# Sheet1.net
KiCad netlist of a schematic drawn in Altium Designer
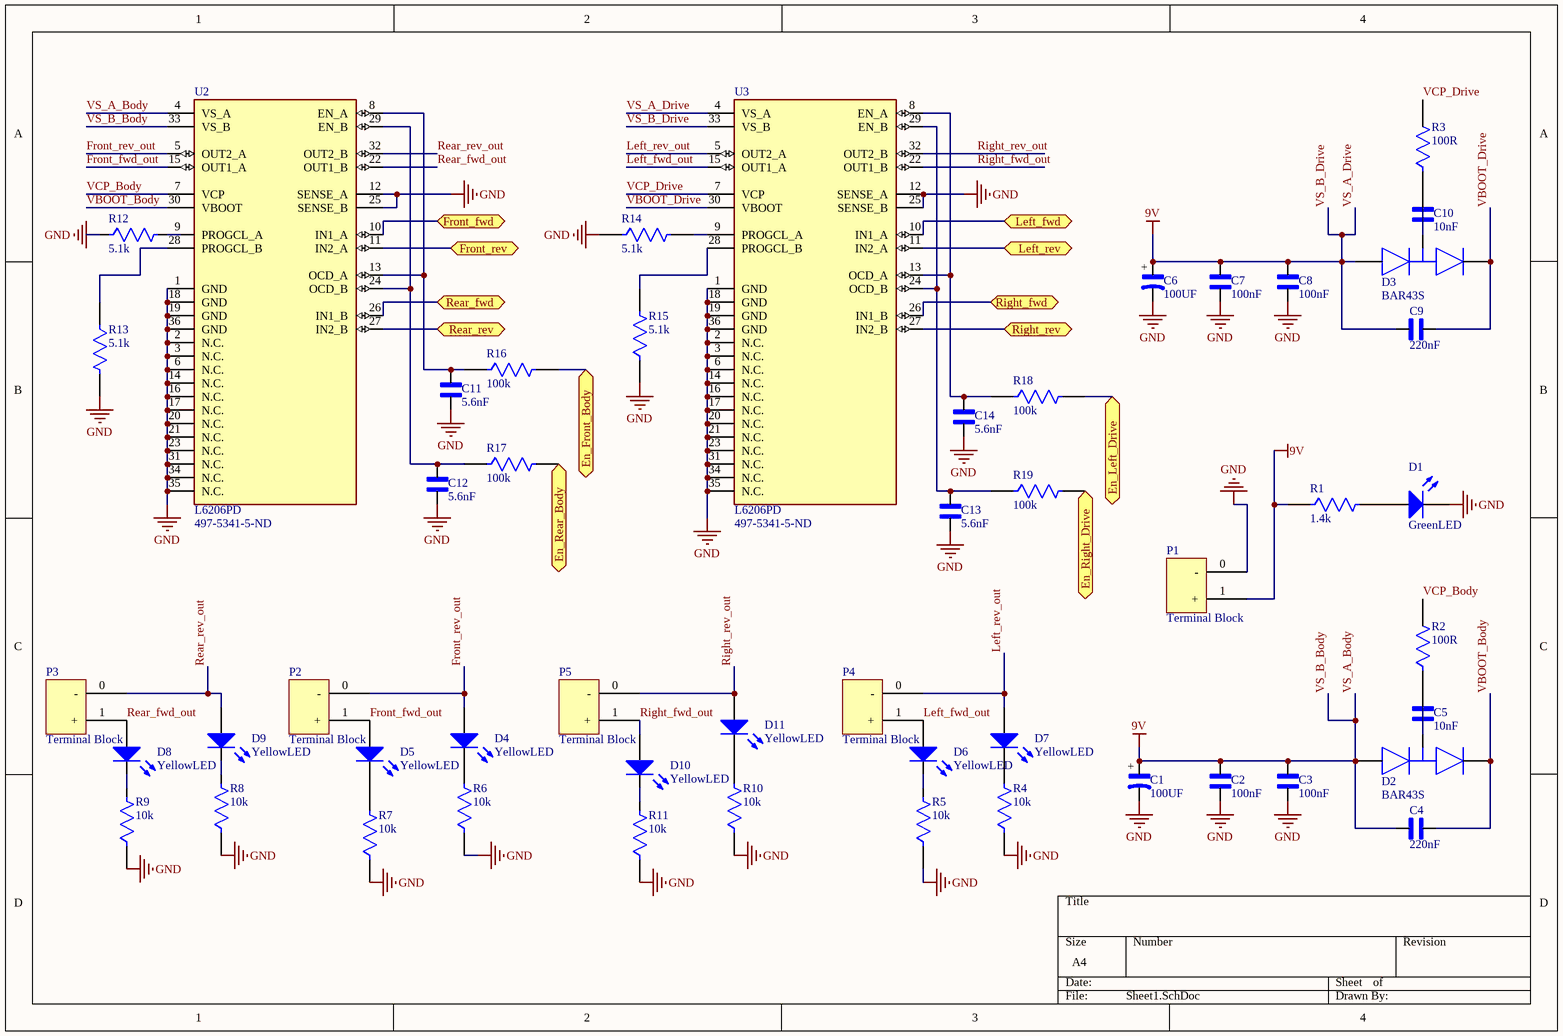
[diagram p0: Sheet1.SchDoc]

(export (version "E")
  (design (tool "Eeschema 10.0.6"))
  (components
    (comp (ref "C1")
      (value "100UF")
      (footprint "100UF")
      (description "Nichicon Aluminium Electrolytic Capacitor 100F 63 V 10mm Through Hole series VZ lifetime 1000h")
      (fields
        (field (name "MANUFACTURER") "Nichicon")
        (field (name "MANUFACTURER PART NUMBER") "UVZ1J101MPD1TD")
      )
      (libsource (lib "Schlib1") (part "100UF Capacitor"))
    )
    (comp (ref "C2")
      (value "100nF")
      (footprint "0402 Capacitor")
      (description "CAP CER 0.1UF 16V X7R 0402")
      (fields
        (field (name "MANUFACTURER") "Murata")
        (field (name "MANUFACTURER PART NUMBER") "GRM155R71C104KA88J")
      )
      (libsource (lib "Schlib1") (part "100nF Capacitor"))
    )
    (comp (ref "C3")
      (value "100nF")
      (footprint "0402 Capacitor")
      (description "CAP CER 0.1UF 16V X7R 0402")
      (fields
        (field (name "MANUFACTURER") "Murata")
        (field (name "MANUFACTURER PART NUMBER") "GRM155R71C104KA88J")
      )
      (libsource (lib "Schlib1") (part "100nF Capacitor"))
    )
    (comp (ref "C4")
      (value "220nF")
      (footprint "0805 Capacitor")
      (description "CAP CER 0805 220NF 100V X7R")
      (fields
        (field (name "MANUFACTURER") "KEMET")
        (field (name "MANUFACTURER PART NUMBER") "C0805C224K1RECAUTO")
      )
      (libsource (lib "Schlib1") (part "220nF Capacitor"))
    )
    (comp (ref "C5")
      (value "10nF")
      (footprint "0402 Capacitor")
      (description "CAP CER 10000PF 50V X7R 0402")
      (fields
        (field (name "MANUFACTURER") "KEMET")
        (field (name "MANUFACTURER PART NUMBER") "C0402C103M5RACTU")
      )
      (libsource (lib "Schlib1") (part "10nF Capacitor"))
    )
    (comp (ref "C6")
      (value "100UF")
      (footprint "100UF")
      (description "Nichicon Aluminium Electrolytic Capacitor 100F 63 V 10mm Through Hole series VZ lifetime 1000h")
      (fields
        (field (name "MANUFACTURER") "Nichicon")
        (field (name "MANUFACTURER PART NUMBER") "UVZ1J101MPD1TD")
      )
      (libsource (lib "Schlib1") (part "100UF Capacitor"))
    )
    (comp (ref "C7")
      (value "100nF")
      (footprint "0402 Capacitor")
      (description "CAP CER 0.1UF 16V X7R 0402")
      (fields
        (field (name "MANUFACTURER") "Murata")
        (field (name "MANUFACTURER PART NUMBER") "GRM155R71C104KA88J")
      )
      (libsource (lib "Schlib1") (part "100nF Capacitor"))
    )
    (comp (ref "C8")
      (value "100nF")
      (footprint "0402 Capacitor")
      (description "CAP CER 0.1UF 16V X7R 0402")
      (fields
        (field (name "MANUFACTURER") "Murata")
        (field (name "MANUFACTURER PART NUMBER") "GRM155R71C104KA88J")
      )
      (libsource (lib "Schlib1") (part "100nF Capacitor"))
    )
    (comp (ref "C9")
      (value "220nF")
      (footprint "0805 Capacitor")
      (description "CAP CER 0805 220NF 100V X7R")
      (fields
        (field (name "MANUFACTURER") "KEMET")
        (field (name "MANUFACTURER PART NUMBER") "C0805C224K1RECAUTO")
      )
      (libsource (lib "Schlib1") (part "220nF Capacitor"))
    )
    (comp (ref "C10")
      (value "10nF")
      (footprint "0402 Capacitor")
      (description "CAP CER 10000PF 50V X7R 0402")
      (fields
        (field (name "MANUFACTURER") "KEMET")
        (field (name "MANUFACTURER PART NUMBER") "C0402C103M5RACTU")
      )
      (libsource (lib "Schlib1") (part "10nF Capacitor"))
    )
    (comp (ref "C11")
      (value "5.6nF")
      (footprint "0402 Capacitor")
      (description "CAP CER 5600PF 25V X7R 0402")
      (fields
        (field (name "MANUFACTURER") "Yageo")
        (field (name "MANUFACTURER PART NUMBER") "CC0402KRX7R8BB562")
      )
      (libsource (lib "Schlib1") (part "5.6nF Capacitor"))
    )
    (comp (ref "C12")
      (value "5.6nF")
      (footprint "0402 Capacitor")
      (description "CAP CER 5600PF 25V X7R 0402")
      (fields
        (field (name "MANUFACTURER") "Yageo")
        (field (name "MANUFACTURER PART NUMBER") "CC0402KRX7R8BB562")
      )
      (libsource (lib "Schlib1") (part "5.6nF Capacitor"))
    )
    (comp (ref "C13")
      (value "5.6nF")
      (footprint "0402 Capacitor")
      (description "CAP CER 5600PF 25V X7R 0402")
      (fields
        (field (name "MANUFACTURER") "Yageo")
        (field (name "MANUFACTURER PART NUMBER") "CC0402KRX7R8BB562")
      )
      (libsource (lib "Schlib1") (part "5.6nF Capacitor"))
    )
    (comp (ref "C14")
      (value "5.6nF")
      (footprint "0402 Capacitor")
      (description "CAP CER 5600PF 25V X7R 0402")
      (fields
        (field (name "MANUFACTURER") "Yageo")
        (field (name "MANUFACTURER PART NUMBER") "CC0402KRX7R8BB562")
      )
      (libsource (lib "Schlib1") (part "5.6nF Capacitor"))
    )
    (comp (ref "D1")
      (value "GreenLED")
      (footprint "LED")
      (description "LED GREEN CLEAR SMD")
      (fields
        (field (name "MANUFACTURER") "Lumex")
        (field (name "MANUFACTURER PART NUMBER") "SML-LXFP0603SUGCTR")
      )
      (libsource (lib "Schlib1") (part "GreenLED"))
    )
    (comp (ref "D2")
      (value "BAR43S")
      (footprint "Double Diode")
      (fields
        (field (name "MANUFACTURER") "STMicroelectronics")
        (field (name "MANUFACTURER PART NUMBER") "BAR43SFILM")
      )
      (libsource (lib "Schlib1") (part "Diode Series"))
    )
    (comp (ref "D3")
      (value "BAR43S")
      (footprint "Double Diode")
      (fields
        (field (name "MANUFACTURER") "STMicroelectronics")
        (field (name "MANUFACTURER PART NUMBER") "BAR43SFILM")
      )
      (libsource (lib "Schlib1") (part "Diode Series"))
    )
    (comp (ref "D4")
      (value "YellowLED")
      (footprint "LED")
      (description "Led Yellow Clear 0603 SMD")
      (fields (field (name "MANUFACTURER") "Inolux") (field (name "MANUFACTURER PART NUMBER") "IN-S63AT5Y"))
      (libsource (lib "Schlib1") (part "YellowLED"))
    )
    (comp (ref "D5")
      (value "YellowLED")
      (footprint "LED")
      (description "Led Yellow Clear 0603 SMD")
      (fields (field (name "MANUFACTURER") "Inolux") (field (name "MANUFACTURER PART NUMBER") "IN-S63AT5Y"))
      (libsource (lib "Schlib1") (part "YellowLED"))
    )
    (comp (ref "D6")
      (value "YellowLED")
      (footprint "LED")
      (description "Led Yellow Clear 0603 SMD")
      (fields (field (name "MANUFACTURER") "Inolux") (field (name "MANUFACTURER PART NUMBER") "IN-S63AT5Y"))
      (libsource (lib "Schlib1") (part "YellowLED"))
    )
    (comp (ref "D7")
      (value "YellowLED")
      (footprint "LED")
      (description "Led Yellow Clear 0603 SMD")
      (fields (field (name "MANUFACTURER") "Inolux") (field (name "MANUFACTURER PART NUMBER") "IN-S63AT5Y"))
      (libsource (lib "Schlib1") (part "YellowLED"))
    )
    (comp (ref "D8")
      (value "YellowLED")
      (footprint "LED")
      (description "Led Yellow Clear 0603 SMD")
      (fields (field (name "MANUFACTURER") "Inolux") (field (name "MANUFACTURER PART NUMBER") "IN-S63AT5Y"))
      (libsource (lib "Schlib1") (part "YellowLED"))
    )
    (comp (ref "D9")
      (value "YellowLED")
      (footprint "LED")
      (description "Led Yellow Clear 0603 SMD")
      (fields (field (name "MANUFACTURER") "Inolux") (field (name "MANUFACTURER PART NUMBER") "IN-S63AT5Y"))
      (libsource (lib "Schlib1") (part "YellowLED"))
    )
    (comp (ref "D10")
      (value "YellowLED")
      (footprint "LED")
      (description "Led Yellow Clear 0603 SMD")
      (fields (field (name "MANUFACTURER") "Inolux") (field (name "MANUFACTURER PART NUMBER") "IN-S63AT5Y"))
      (libsource (lib "Schlib1") (part "YellowLED"))
    )
    (comp (ref "D11")
      (value "YellowLED")
      (footprint "LED")
      (description "Led Yellow Clear 0603 SMD")
      (fields (field (name "MANUFACTURER") "Inolux") (field (name "MANUFACTURER PART NUMBER") "IN-S63AT5Y"))
      (libsource (lib "Schlib1") (part "YellowLED"))
    )
    (comp (ref "P1")
      (value "Terminal Block")
      (footprint "PHOENIX_1935161")
      (description "Conn Terminal Blocks 2 POS 5mm Solder ST Thru-Hole 16A")
      (fields
        (field (name "MANUFACTURER") "Phoenix Contact")
        (field (name "MANUFACTURER PART NUMBER") "1935161")
      )
      (libsource (lib "Schlib1") (part "1935161"))
    )
    (comp (ref "P2")
      (value "Terminal Block")
      (footprint "PHOENIX_1935161")
      (description "Conn Terminal Blocks 2 POS 5mm Solder ST Thru-Hole 16A")
      (fields
        (field (name "MANUFACTURER") "Phoenix Contact")
        (field (name "MANUFACTURER PART NUMBER") "1935161")
      )
      (libsource (lib "Schlib1") (part "1935161"))
    )
    (comp (ref "P3")
      (value "Terminal Block")
      (footprint "PHOENIX_1935161")
      (description "Conn Terminal Blocks 2 POS 5mm Solder ST Thru-Hole 16A")
      (fields
        (field (name "MANUFACTURER") "Phoenix Contact")
        (field (name "MANUFACTURER PART NUMBER") "1935161")
      )
      (libsource (lib "Schlib1") (part "1935161"))
    )
    (comp (ref "P4")
      (value "Terminal Block")
      (footprint "PHOENIX_1935161")
      (description "Conn Terminal Blocks 2 POS 5mm Solder ST Thru-Hole 16A")
      (fields
        (field (name "MANUFACTURER") "Phoenix Contact")
        (field (name "MANUFACTURER PART NUMBER") "1935161")
      )
      (libsource (lib "Schlib1") (part "1935161"))
    )
    (comp (ref "P5")
      (value "Terminal Block")
      (footprint "PHOENIX_1935161")
      (description "Conn Terminal Blocks 2 POS 5mm Solder ST Thru-Hole 16A")
      (fields
        (field (name "MANUFACTURER") "Phoenix Contact")
        (field (name "MANUFACTURER PART NUMBER") "1935161")
      )
      (libsource (lib "Schlib1") (part "1935161"))
    )
    (comp (ref "R1")
      (value "1.4k")
      (footprint "0402 Resistor")
      (description "RES SMD 14K OHM 0.1% 1/16W 0402")
      (fields
        (field (name "MANUFACTURER") "Panasonic")
        (field (name "MANUFACTURER PART NUMBER") "ERA-2AEB1402X")
      )
      (libsource (lib "Schlib1") (part "1.4k Resistor"))
    )
    (comp (ref "R2")
      (value "100R")
      (footprint "0805 Resistor")
      (description "RESISTOR, SURGE, 0805, 1%, 100R")
      (fields
        (field (name "MANUFACTURER") "Panasonic")
        (field (name "MANUFACTURER PART NUMBER") "ERJ-P06F1000V")
      )
      (libsource (lib "Schlib1") (part "100R Resistor"))
    )
    (comp (ref "R3")
      (value "100R")
      (footprint "0805 Resistor")
      (description "RESISTOR, SURGE, 0805, 1%, 100R")
      (fields
        (field (name "MANUFACTURER") "Panasonic")
        (field (name "MANUFACTURER PART NUMBER") "ERJ-P06F1000V")
      )
      (libsource (lib "Schlib1") (part "100R Resistor"))
    )
    (comp (ref "R4")
      (value "10k")
      (footprint "0402 Resistor")
      (description "Res Thin Film 0402 10K Ohm 0.5% 0.063W(1/16W) ±25ppm/C Molded SMD Automotive Punched T/R")
      (fields
        (field (name "MANUFACTURER") "Panasonic")
        (field (name "MANUFACTURER PART NUMBER") "ERA-2AED103X")
      )
      (libsource (lib "Schlib1") (part "10k Resistor"))
    )
    (comp (ref "R5")
      (value "10k")
      (footprint "0402 Resistor")
      (description "Res Thin Film 0402 10K Ohm 0.5% 0.063W(1/16W) ±25ppm/C Molded SMD Automotive Punched T/R")
      (fields
        (field (name "MANUFACTURER") "Panasonic")
        (field (name "MANUFACTURER PART NUMBER") "ERA-2AED103X")
      )
      (libsource (lib "Schlib1") (part "10k Resistor"))
    )
    (comp (ref "R6")
      (value "10k")
      (footprint "0402 Resistor")
      (description "Res Thin Film 0402 10K Ohm 0.5% 0.063W(1/16W) ±25ppm/C Molded SMD Automotive Punched T/R")
      (fields
        (field (name "MANUFACTURER") "Panasonic")
        (field (name "MANUFACTURER PART NUMBER") "ERA-2AED103X")
      )
      (libsource (lib "Schlib1") (part "10k Resistor"))
    )
    (comp (ref "R7")
      (value "10k")
      (footprint "0402 Resistor")
      (description "Res Thin Film 0402 10K Ohm 0.5% 0.063W(1/16W) ±25ppm/C Molded SMD Automotive Punched T/R")
      (fields
        (field (name "MANUFACTURER") "Panasonic")
        (field (name "MANUFACTURER PART NUMBER") "ERA-2AED103X")
      )
      (libsource (lib "Schlib1") (part "10k Resistor"))
    )
    (comp (ref "R8")
      (value "10k")
      (footprint "0402 Resistor")
      (description "Res Thin Film 0402 10K Ohm 0.5% 0.063W(1/16W) ±25ppm/C Molded SMD Automotive Punched T/R")
      (fields
        (field (name "MANUFACTURER") "Panasonic")
        (field (name "MANUFACTURER PART NUMBER") "ERA-2AED103X")
      )
      (libsource (lib "Schlib1") (part "10k Resistor"))
    )
    (comp (ref "R9")
      (value "10k")
      (footprint "0402 Resistor")
      (description "Res Thin Film 0402 10K Ohm 0.5% 0.063W(1/16W) ±25ppm/C Molded SMD Automotive Punched T/R")
      (fields
        (field (name "MANUFACTURER") "Panasonic")
        (field (name "MANUFACTURER PART NUMBER") "ERA-2AED103X")
      )
      (libsource (lib "Schlib1") (part "10k Resistor"))
    )
    (comp (ref "R10")
      (value "10k")
      (footprint "0402 Resistor")
      (description "Res Thin Film 0402 10K Ohm 0.5% 0.063W(1/16W) ±25ppm/C Molded SMD Automotive Punched T/R")
      (fields
        (field (name "MANUFACTURER") "Panasonic")
        (field (name "MANUFACTURER PART NUMBER") "ERA-2AED103X")
      )
      (libsource (lib "Schlib1") (part "10k Resistor"))
    )
    (comp (ref "R11")
      (value "10k")
      (footprint "0402 Resistor")
      (description "Res Thin Film 0402 10K Ohm 0.5% 0.063W(1/16W) ±25ppm/C Molded SMD Automotive Punched T/R")
      (fields
        (field (name "MANUFACTURER") "Panasonic")
        (field (name "MANUFACTURER PART NUMBER") "ERA-2AED103X")
      )
      (libsource (lib "Schlib1") (part "10k Resistor"))
    )
    (comp (ref "R12")
      (value "5.1k")
      (footprint "0402 Resistor")
      (fields
        (field (name "MANUFACTURER") "Panasonic")
        (field (name "MANUFACTURER PART NUMBER") "ERJ-2RKF5101X")
        (field (name "TOLERANCE") "1%")
      )
      (libsource (lib "Schlib1") (part "5.1k Resistor"))
    )
    (comp (ref "R13")
      (value "5.1k")
      (footprint "0402 Resistor")
      (fields
        (field (name "MANUFACTURER") "Panasonic")
        (field (name "MANUFACTURER PART NUMBER") "ERJ-2RKF5101X")
        (field (name "TOLERANCE") "1%")
      )
      (libsource (lib "Schlib1") (part "5.1k Resistor"))
    )
    (comp (ref "R14")
      (value "5.1k")
      (footprint "0402 Resistor")
      (fields
        (field (name "MANUFACTURER") "Panasonic")
        (field (name "MANUFACTURER PART NUMBER") "ERJ-2RKF5101X")
        (field (name "TOLERANCE") "1%")
      )
      (libsource (lib "Schlib1") (part "5.1k Resistor"))
    )
    (comp (ref "R15")
      (value "5.1k")
      (footprint "0402 Resistor")
      (fields
        (field (name "MANUFACTURER") "Panasonic")
        (field (name "MANUFACTURER PART NUMBER") "ERJ-2RKF5101X")
        (field (name "TOLERANCE") "1%")
      )
      (libsource (lib "Schlib1") (part "5.1k Resistor"))
    )
    (comp (ref "R16")
      (value "100k")
      (footprint "0805 Resistor")
      (description "YAGEO         RC0805FR-07100KL            RES, THICK FILM, 100K, 1%, 0.125W, 0805, REEL")
      (fields
        (field (name "MANUFACTURER") "Yageo")
        (field (name "MANUFACTURER PART NUMBER") "RC0805FR-07100KL")
      )
      (libsource (lib "Schlib1") (part "100k Resistor"))
    )
    (comp (ref "R17")
      (value "100k")
      (footprint "0805 Resistor")
      (description "YAGEO         RC0805FR-07100KL            RES, THICK FILM, 100K, 1%, 0.125W, 0805, REEL")
      (fields
        (field (name "MANUFACTURER") "Yageo")
        (field (name "MANUFACTURER PART NUMBER") "RC0805FR-07100KL")
      )
      (libsource (lib "Schlib1") (part "100k Resistor"))
    )
    (comp (ref "R18")
      (value "100k")
      (footprint "0805 Resistor")
      (description "YAGEO         RC0805FR-07100KL            RES, THICK FILM, 100K, 1%, 0.125W, 0805, REEL")
      (fields
        (field (name "MANUFACTURER") "Yageo")
        (field (name "MANUFACTURER PART NUMBER") "RC0805FR-07100KL")
      )
      (libsource (lib "Schlib1") (part "100k Resistor"))
    )
    (comp (ref "R19")
      (value "100k")
      (footprint "0805 Resistor")
      (description "YAGEO         RC0805FR-07100KL            RES, THICK FILM, 100K, 1%, 0.125W, 0805, REEL")
      (fields
        (field (name "MANUFACTURER") "Yageo")
        (field (name "MANUFACTURER PART NUMBER") "RC0805FR-07100KL")
      )
      (libsource (lib "Schlib1") (part "100k Resistor"))
    )
    (comp (ref "U2")
      (value "L6206PD")
      (footprint "L6206PD")
      (description "Bridge Driver IC PowerSO-36, L6206PD, ST")
      (fields
        (field (name "MANUFACTURER") "STMicroelectronics")
        (field (name "SUPPLIER PART NUMBER 1") "497-5341-5-ND")
      )
      (libsource (lib "Schlib1") (part "L6206PD"))
    )
    (comp (ref "U3")
      (value "L6206PD")
      (footprint "L6206PD")
      (description "Bridge Driver IC PowerSO-36, L6206PD, ST")
      (fields
        (field (name "MANUFACTURER") "STMicroelectronics")
        (field (name "SUPPLIER PART NUMBER 1") "497-5341-5-ND")
      )
      (libsource (lib "Schlib1") (part "L6206PD"))
    )
  )
  (nets
    (net (code "1") (name "/En_Front_Body") (class "Default")
      (node (ref "R16") (pin "2") (pinfunction "2_2") (pintype "passive"))
    )
    (net (code "2") (name "/En_Left_Drive") (class "Default")
      (node (ref "R18") (pin "2") (pinfunction "2_2") (pintype "passive"))
    )
    (net (code "3") (name "/En_Rear_Body") (class "Default")
      (node (ref "R17") (pin "2") (pinfunction "2_2") (pintype "passive"))
    )
    (net (code "4") (name "/En_Right_Drive") (class "Default")
      (node (ref "R19") (pin "2") (pinfunction "2_2") (pintype "passive"))
    )
    (net (code "5") (name "/Front_fwd") (class "Default")
      (node (ref "U2") (pin "10") (pinfunction "IN1_A_10") (pintype "bidirectional"))
    )
    (net (code "6") (name "/Front_fwd_out") (class "Default")
      (node (ref "D5") (pin "1") (pinfunction "A_1") (pintype "passive"))
      (node (ref "P2") (pin "1") (pinfunction "+_1") (pintype "passive"))
      (node (ref "U2") (pin "15") (pinfunction "OUT1_A_15") (pintype "bidirectional"))
    )
    (net (code "7") (name "/Front_rev") (class "Default")
      (node (ref "U2") (pin "11") (pinfunction "IN2_A_11") (pintype "bidirectional"))
    )
    (net (code "8") (name "/Front_rev_out") (class "Default")
      (node (ref "D4") (pin "1") (pinfunction "A_1") (pintype "passive"))
      (node (ref "P2") (pin "0") (pinfunction "-_0") (pintype "passive"))
      (node (ref "U2") (pin "5") (pinfunction "OUT2_A_5") (pintype "bidirectional"))
    )
    (net (code "9") (name "/Left_fwd") (class "Default")
      (node (ref "U3") (pin "10") (pinfunction "IN1_A_10") (pintype "bidirectional"))
    )
    (net (code "10") (name "/Left_fwd_out") (class "Default")
      (node (ref "D6") (pin "1") (pinfunction "A_1") (pintype "passive"))
      (node (ref "P4") (pin "1") (pinfunction "+_1") (pintype "passive"))
      (node (ref "U3") (pin "15") (pinfunction "OUT1_A_15") (pintype "bidirectional"))
    )
    (net (code "11") (name "/Left_rev") (class "Default")
      (node (ref "U3") (pin "11") (pinfunction "IN2_A_11") (pintype "bidirectional"))
    )
    (net (code "12") (name "/Left_rev_out") (class "Default")
      (node (ref "D7") (pin "1") (pinfunction "A_1") (pintype "passive"))
      (node (ref "P4") (pin "0") (pinfunction "-_0") (pintype "passive"))
      (node (ref "U3") (pin "5") (pinfunction "OUT2_A_5") (pintype "bidirectional"))
    )
    (net (code "13") (name "/Rear_fwd") (class "Default")
      (node (ref "U2") (pin "26") (pinfunction "IN1_B_26") (pintype "bidirectional"))
    )
    (net (code "14") (name "/Rear_fwd_out") (class "Default")
      (node (ref "D8") (pin "1") (pinfunction "A_1") (pintype "passive"))
      (node (ref "P3") (pin "1") (pinfunction "+_1") (pintype "passive"))
      (node (ref "U2") (pin "22") (pinfunction "OUT1_B_22") (pintype "bidirectional"))
    )
    (net (code "15") (name "/Rear_rev") (class "Default")
      (node (ref "U2") (pin "27") (pinfunction "IN2_B_27") (pintype "bidirectional"))
    )
    (net (code "16") (name "/Rear_rev_out") (class "Default")
      (node (ref "D9") (pin "1") (pinfunction "A_1") (pintype "passive"))
      (node (ref "P3") (pin "0") (pinfunction "-_0") (pintype "passive"))
      (node (ref "U2") (pin "32") (pinfunction "OUT2_B_32") (pintype "bidirectional"))
    )
    (net (code "17") (name "/Right_fwd") (class "Default")
      (node (ref "U3") (pin "26") (pinfunction "IN1_B_26") (pintype "bidirectional"))
    )
    (net (code "18") (name "/Right_fwd_out") (class "Default")
      (node (ref "D10") (pin "1") (pinfunction "A_1") (pintype "passive"))
      (node (ref "P5") (pin "1") (pinfunction "+_1") (pintype "passive"))
      (node (ref "U3") (pin "22") (pinfunction "OUT1_B_22") (pintype "bidirectional"))
    )
    (net (code "19") (name "/Right_rev") (class "Default")
      (node (ref "U3") (pin "27") (pinfunction "IN2_B_27") (pintype "bidirectional"))
    )
    (net (code "20") (name "/Right_rev_out") (class "Default")
      (node (ref "D11") (pin "1") (pinfunction "A_1") (pintype "passive"))
      (node (ref "P5") (pin "0") (pinfunction "-_0") (pintype "passive"))
      (node (ref "U3") (pin "32") (pinfunction "OUT2_B_32") (pintype "bidirectional"))
    )
    (net (code "21") (name "/VBOOT_Body") (class "Default")
      (node (ref "C4") (pin "2") (pinfunction "2_2") (pintype "passive"))
      (node (ref "D2") (pin "2") (pinfunction "K1_2") (pintype "passive"))
      (node (ref "U2") (pin "30") (pinfunction "VBOOT_30") (pintype "power_in"))
    )
    (net (code "22") (name "/VBOOT_Drive") (class "Default")
      (node (ref "C9") (pin "2") (pinfunction "2_2") (pintype "passive"))
      (node (ref "D3") (pin "2") (pinfunction "K1_2") (pintype "passive"))
      (node (ref "U3") (pin "30") (pinfunction "VBOOT_30") (pintype "power_in"))
    )
    (net (code "23") (name "/VCP_Body") (class "Default")
      (node (ref "R2") (pin "2") (pinfunction "2_2") (pintype "passive"))
      (node (ref "U2") (pin "7") (pinfunction "VCP_7") (pintype "power_in"))
    )
    (net (code "24") (name "/VCP_Drive") (class "Default")
      (node (ref "R3") (pin "2") (pinfunction "2_2") (pintype "passive"))
      (node (ref "U3") (pin "7") (pinfunction "VCP_7") (pintype "power_in"))
    )
    (net (code "25") (name "9V") (class "Default")
      (node (ref "C1") (pin "+") (pintype "passive"))
      (node (ref "C2") (pin "2") (pinfunction "2_2") (pintype "passive"))
      (node (ref "C3") (pin "2") (pinfunction "2_2") (pintype "passive"))
      (node (ref "C4") (pin "1") (pinfunction "1_1") (pintype "passive"))
      (node (ref "C6") (pin "+") (pintype "passive"))
      (node (ref "C7") (pin "2") (pinfunction "2_2") (pintype "passive"))
      (node (ref "C8") (pin "2") (pinfunction "2_2") (pintype "passive"))
      (node (ref "C9") (pin "1") (pinfunction "1_1") (pintype "passive"))
      (node (ref "D2") (pin "1") (pinfunction "A2_1") (pintype "passive"))
      (node (ref "D3") (pin "1") (pinfunction "A2_1") (pintype "passive"))
      (node (ref "P1") (pin "1") (pinfunction "+_1") (pintype "passive"))
      (node (ref "R1") (pin "1") (pinfunction "1_1") (pintype "passive"))
      (node (ref "U2") (pin "33") (pinfunction "VS_B_33") (pintype "power_in"))
      (node (ref "U2") (pin "4") (pinfunction "VS_A_4") (pintype "power_in"))
      (node (ref "U3") (pin "33") (pinfunction "VS_B_33") (pintype "power_in"))
      (node (ref "U3") (pin "4") (pinfunction "VS_A_4") (pintype "power_in"))
    )
    (net (code "26") (name "GND") (class "Default")
      (node (ref "C1") (pin "1") (pinfunction "1_1") (pintype "passive"))
      (node (ref "C11") (pin "1") (pinfunction "1_1") (pintype "passive"))
      (node (ref "C12") (pin "1") (pinfunction "1_1") (pintype "passive"))
      (node (ref "C13") (pin "1") (pinfunction "1_1") (pintype "passive"))
      (node (ref "C14") (pin "1") (pinfunction "1_1") (pintype "passive"))
      (node (ref "C2") (pin "1") (pinfunction "1_1") (pintype "passive"))
      (node (ref "C3") (pin "1") (pinfunction "1_1") (pintype "passive"))
      (node (ref "C6") (pin "1") (pinfunction "1_1") (pintype "passive"))
      (node (ref "C7") (pin "1") (pinfunction "1_1") (pintype "passive"))
      (node (ref "C8") (pin "1") (pinfunction "1_1") (pintype "passive"))
      (node (ref "D1") (pin "2") (pinfunction "K_2") (pintype "passive"))
      (node (ref "P1") (pin "0") (pinfunction "-_0") (pintype "passive"))
      (node (ref "R10") (pin "1") (pinfunction "1_1") (pintype "passive"))
      (node (ref "R11") (pin "1") (pinfunction "1_1") (pintype "passive"))
      (node (ref "R12") (pin "1") (pinfunction "1_1") (pintype "passive"))
      (node (ref "R13") (pin "2") (pinfunction "2_2") (pintype "passive"))
      (node (ref "R14") (pin "1") (pinfunction "1_1") (pintype "passive"))
      (node (ref "R15") (pin "1") (pinfunction "1_1") (pintype "passive"))
      (node (ref "R4") (pin "1") (pinfunction "1_1") (pintype "passive"))
      (node (ref "R5") (pin "1") (pinfunction "1_1") (pintype "passive"))
      (node (ref "R6") (pin "1") (pinfunction "1_1") (pintype "passive"))
      (node (ref "R7") (pin "1") (pinfunction "1_1") (pintype "passive"))
      (node (ref "R8") (pin "1") (pinfunction "1_1") (pintype "passive"))
      (node (ref "R9") (pin "1") (pinfunction "1_1") (pintype "passive"))
      (node (ref "U2") (pin "1") (pinfunction "GND_1") (pintype "power_in"))
      (node (ref "U2") (pin "12") (pinfunction "SENSE_A_12") (pintype "power_in"))
      (node (ref "U2") (pin "14") (pinfunction "N.C._14") (pintype "power_in"))
      (node (ref "U2") (pin "16") (pinfunction "N.C._16") (pintype "power_in"))
      (node (ref "U2") (pin "17") (pinfunction "N.C._17") (pintype "power_in"))
      (node (ref "U2") (pin "18") (pinfunction "GND_18") (pintype "power_in"))
      (node (ref "U2") (pin "19") (pinfunction "GND_19") (pintype "power_in"))
      (node (ref "U2") (pin "2") (pinfunction "N.C._2") (pintype "power_in"))
      (node (ref "U2") (pin "20") (pinfunction "N.C._20") (pintype "power_in"))
      (node (ref "U2") (pin "21") (pinfunction "N.C._21") (pintype "power_in"))
      (node (ref "U2") (pin "23") (pinfunction "N.C._23") (pintype "power_in"))
      (node (ref "U2") (pin "25") (pinfunction "SENSE_B_25") (pintype "power_in"))
      (node (ref "U2") (pin "3") (pinfunction "N.C._3") (pintype "power_in"))
      (node (ref "U2") (pin "31") (pinfunction "N.C._31") (pintype "power_in"))
      (node (ref "U2") (pin "34") (pinfunction "N.C._34") (pintype "power_in"))
      (node (ref "U2") (pin "35") (pinfunction "N.C._35") (pintype "power_in"))
      (node (ref "U2") (pin "36") (pinfunction "GND_36") (pintype "power_in"))
      (node (ref "U2") (pin "6") (pinfunction "N.C._6") (pintype "power_in"))
      (node (ref "U3") (pin "1") (pinfunction "GND_1") (pintype "power_in"))
      (node (ref "U3") (pin "12") (pinfunction "SENSE_A_12") (pintype "power_in"))
      (node (ref "U3") (pin "14") (pinfunction "N.C._14") (pintype "power_in"))
      (node (ref "U3") (pin "16") (pinfunction "N.C._16") (pintype "power_in"))
      (node (ref "U3") (pin "17") (pinfunction "N.C._17") (pintype "power_in"))
      (node (ref "U3") (pin "18") (pinfunction "GND_18") (pintype "power_in"))
      (node (ref "U3") (pin "19") (pinfunction "GND_19") (pintype "power_in"))
      (node (ref "U3") (pin "2") (pinfunction "N.C._2") (pintype "power_in"))
      (node (ref "U3") (pin "20") (pinfunction "N.C._20") (pintype "power_in"))
      (node (ref "U3") (pin "21") (pinfunction "N.C._21") (pintype "power_in"))
      (node (ref "U3") (pin "23") (pinfunction "N.C._23") (pintype "power_in"))
      (node (ref "U3") (pin "25") (pinfunction "SENSE_B_25") (pintype "power_in"))
      (node (ref "U3") (pin "3") (pinfunction "N.C._3") (pintype "power_in"))
      (node (ref "U3") (pin "31") (pinfunction "N.C._31") (pintype "power_in"))
      (node (ref "U3") (pin "34") (pinfunction "N.C._34") (pintype "power_in"))
      (node (ref "U3") (pin "35") (pinfunction "N.C._35") (pintype "power_in"))
      (node (ref "U3") (pin "36") (pinfunction "GND_36") (pintype "power_in"))
      (node (ref "U3") (pin "6") (pinfunction "N.C._6") (pintype "power_in"))
    )
    (net (code "27") (name "Net-(C5-Pad1)") (class "Default")
      (node (ref "C5") (pin "1") (pinfunction "1_1") (pintype "passive"))
      (node (ref "D2") (pin "3") (pinfunction "3_3") (pintype "passive"))
    )
    (net (code "28") (name "Net-(C5-Pad2)") (class "Default")
      (node (ref "C5") (pin "2") (pinfunction "2_2") (pintype "passive"))
      (node (ref "R2") (pin "1") (pinfunction "1_1") (pintype "passive"))
    )
    (net (code "29") (name "Net-(C10-Pad1)") (class "Default")
      (node (ref "C10") (pin "1") (pinfunction "1_1") (pintype "passive"))
      (node (ref "D3") (pin "3") (pinfunction "3_3") (pintype "passive"))
    )
    (net (code "30") (name "Net-(C10-Pad2)") (class "Default")
      (node (ref "C10") (pin "2") (pinfunction "2_2") (pintype "passive"))
      (node (ref "R3") (pin "1") (pinfunction "1_1") (pintype "passive"))
    )
    (net (code "31") (name "Net-(D1-A)") (class "Default")
      (node (ref "D1") (pin "1") (pinfunction "A_1") (pintype "passive"))
      (node (ref "R1") (pin "2") (pinfunction "2_2") (pintype "passive"))
    )
    (net (code "32") (name "Net-(D5-K)") (class "Default")
      (node (ref "D5") (pin "2") (pinfunction "K_2") (pintype "passive"))
      (node (ref "R7") (pin "2") (pinfunction "2_2") (pintype "passive"))
    )
    (net (code "33") (name "Net-(D6-K)") (class "Default")
      (node (ref "D6") (pin "2") (pinfunction "K_2") (pintype "passive"))
      (node (ref "R5") (pin "2") (pinfunction "2_2") (pintype "passive"))
    )
    (net (code "34") (name "Net-(D8-K)") (class "Default")
      (node (ref "D8") (pin "2") (pinfunction "K_2") (pintype "passive"))
      (node (ref "R9") (pin "2") (pinfunction "2_2") (pintype "passive"))
    )
    (net (code "35") (name "Net-(D9-K)") (class "Default")
      (node (ref "D9") (pin "2") (pinfunction "K_2") (pintype "passive"))
      (node (ref "R8") (pin "2") (pinfunction "2_2") (pintype "passive"))
    )
    (net (code "36") (name "Net-(D10-K)") (class "Default")
      (node (ref "D10") (pin "2") (pinfunction "K_2") (pintype "passive"))
      (node (ref "R11") (pin "2") (pinfunction "2_2") (pintype "passive"))
    )
    (net (code "37") (name "Net-(D11-K)") (class "Default")
      (node (ref "D11") (pin "2") (pinfunction "K_2") (pintype "passive"))
      (node (ref "R10") (pin "2") (pinfunction "2_2") (pintype "passive"))
    )
    (net (code "38") (name "Net-(U2-EN_A)") (class "Default")
      (node (ref "C11") (pin "2") (pinfunction "2_2") (pintype "passive"))
      (node (ref "R16") (pin "1") (pinfunction "1_1") (pintype "passive"))
      (node (ref "U2") (pin "13") (pinfunction "OCD_A_13") (pintype "bidirectional"))
      (node (ref "U2") (pin "8") (pinfunction "EN_A_8") (pintype "bidirectional"))
    )
    (net (code "39") (name "Net-(U2-EN_B)") (class "Default")
      (node (ref "C12") (pin "2") (pinfunction "2_2") (pintype "passive"))
      (node (ref "R17") (pin "1") (pinfunction "1_1") (pintype "passive"))
      (node (ref "U2") (pin "24") (pinfunction "OCD_B_24") (pintype "bidirectional"))
      (node (ref "U2") (pin "29") (pinfunction "EN_B_29") (pintype "bidirectional"))
    )
    (net (code "40") (name "Net-(U2-PROGCL_A)") (class "Default")
      (node (ref "R12") (pin "2") (pinfunction "2_2") (pintype "passive"))
      (node (ref "U2") (pin "9") (pinfunction "PROGCL_A_9") (pintype "power_in"))
    )
    (net (code "41") (name "Net-(U2-PROGCL_B)") (class "Default")
      (node (ref "R13") (pin "1") (pinfunction "1_1") (pintype "passive"))
      (node (ref "U2") (pin "28") (pinfunction "PROGCL_B_28") (pintype "power_in"))
    )
    (net (code "42") (name "Net-(U3-EN_A)") (class "Default")
      (node (ref "C14") (pin "2") (pinfunction "2_2") (pintype "passive"))
      (node (ref "R18") (pin "1") (pinfunction "1_1") (pintype "passive"))
      (node (ref "U3") (pin "13") (pinfunction "OCD_A_13") (pintype "bidirectional"))
      (node (ref "U3") (pin "8") (pinfunction "EN_A_8") (pintype "bidirectional"))
    )
    (net (code "43") (name "Net-(U3-EN_B)") (class "Default")
      (node (ref "C13") (pin "2") (pinfunction "2_2") (pintype "passive"))
      (node (ref "R19") (pin "1") (pinfunction "1_1") (pintype "passive"))
      (node (ref "U3") (pin "24") (pinfunction "OCD_B_24") (pintype "bidirectional"))
      (node (ref "U3") (pin "29") (pinfunction "EN_B_29") (pintype "bidirectional"))
    )
    (net (code "44") (name "Net-(U3-PROGCL_A)") (class "Default")
      (node (ref "R14") (pin "2") (pinfunction "2_2") (pintype "passive"))
      (node (ref "U3") (pin "9") (pinfunction "PROGCL_A_9") (pintype "power_in"))
    )
    (net (code "45") (name "Net-(U3-PROGCL_B)") (class "Default")
      (node (ref "R15") (pin "2") (pinfunction "2_2") (pintype "passive"))
      (node (ref "U3") (pin "28") (pinfunction "PROGCL_B_28") (pintype "power_in"))
    )
    (net (code "46") (name "unconnected-(D4-K-Pad2)") (class "Default")
      (node (ref "D4") (pin "2") (pinfunction "K_2") (pintype "passive"))
    )
    (net (code "47") (name "unconnected-(D7-K-Pad2)") (class "Default")
      (node (ref "D7") (pin "2") (pinfunction "K_2") (pintype "passive"))
    )
    (net (code "48") (name "unconnected-(R4-Pad2)") (class "Default")
      (node (ref "R4") (pin "2") (pinfunction "2_2") (pintype "passive"))
    )
    (net (code "49") (name "unconnected-(R6-Pad2)") (class "Default")
      (node (ref "R6") (pin "2") (pinfunction "2_2") (pintype "passive"))
    )
  )
)
